# adon3AA.net
KiCad netlist of a schematic drawn in EAGLE
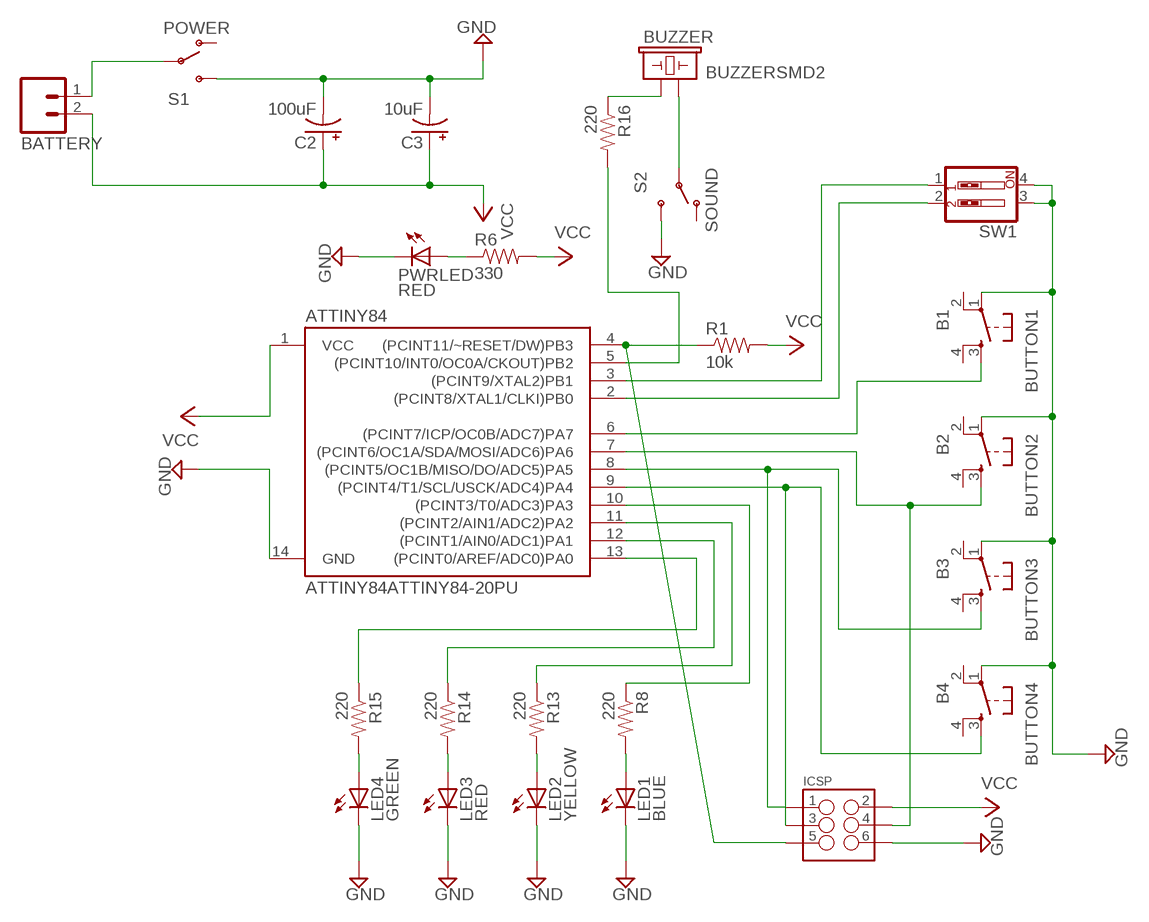
[diagram p0: schematic, sheet 1]

(export (version "E")
  (design (tool "Eeschema 10.0.6"))
  (components
    (comp (ref "ATTINY84")
      (value "ATTINY84ATTINY84-20PU")
      (footprint "eagle-import:DIL14")
      (libsource (lib "eagle-import") (part "ATTINY84ATTINY84-20PU"))
    )
    (comp (ref "BATTERY")
      (value "M02JST-PTH-2")
      (footprint "eagle-import:JST-2-PTH")
      (libsource (lib "eagle-import") (part "M02JST-PTH-2"))
    )
    (comp (ref "BUTTON1")
      (value "B1")
      (footprint "eagle-import:TACTILE-PTH")
      (libsource (lib "eagle-import") (part "TAC_SWITCHPTH"))
    )
    (comp (ref "BUTTON2")
      (value "B2")
      (footprint "eagle-import:TACTILE-PTH")
      (libsource (lib "eagle-import") (part "TAC_SWITCHPTH"))
    )
    (comp (ref "BUTTON3")
      (value "B3")
      (footprint "eagle-import:TACTILE-PTH")
      (libsource (lib "eagle-import") (part "TAC_SWITCHPTH"))
    )
    (comp (ref "BUTTON4")
      (value "B4")
      (footprint "eagle-import:TACTILE-PTH")
      (libsource (lib "eagle-import") (part "TAC_SWITCHPTH"))
    )
    (comp (ref "BUZZER")
      (value "BUZZERSMD2")
      (footprint "eagle-import:BUZZER-CCV")
      (libsource (lib "eagle-import") (part "BUZZERSMD2"))
    )
    (comp (ref "C2")
      (value "100uF")
      (footprint "eagle-import:CPOL-RADIAL-100UF-25V")
      (libsource (lib "eagle-import") (part "CAP_POLPTH1"))
    )
    (comp (ref "C3")
      (value "10uF")
      (footprint "eagle-import:CPOL-RADIAL-10UF-25V")
      (libsource (lib "eagle-import") (part "CAP_POLPTH2"))
    )
    (comp (ref "ICSP")
      (value "M03X2NO_SILK")
      (footprint "eagle-import:2X3-NS")
      (libsource (lib "eagle-import") (part "M03X2NO_SILK"))
    )
    (comp (ref "LED1")
      (value "BLUE")
      (footprint "eagle-import:LED5MM")
      (libsource (lib "eagle-import") (part "LED5MM"))
    )
    (comp (ref "LED2")
      (value "YELLOW")
      (footprint "eagle-import:LED5MM")
      (libsource (lib "eagle-import") (part "LED5MM"))
    )
    (comp (ref "LED3")
      (value "RED")
      (footprint "eagle-import:LED5MM")
      (libsource (lib "eagle-import") (part "LED5MM"))
    )
    (comp (ref "LED4")
      (value "GREEN")
      (footprint "eagle-import:LED5MM")
      (libsource (lib "eagle-import") (part "LED5MM"))
    )
    (comp (ref "PWRLED")
      (value "RED")
      (footprint "eagle-import:LED3MM")
      (libsource (lib "eagle-import") (part "LED3MM"))
    )
    (comp (ref "R1")
      (value "10k")
      (footprint "eagle-import:AXIAL-0.4")
      (libsource (lib "eagle-import") (part "RESISTORPTH-1/4W"))
    )
    (comp (ref "R6")
      (value "330")
      (footprint "eagle-import:AXIAL-0.4")
      (libsource (lib "eagle-import") (part "RESISTORPTH-1/4W"))
    )
    (comp (ref "R8")
      (value "220")
      (footprint "eagle-import:AXIAL-0.4")
      (libsource (lib "eagle-import") (part "RESISTORPTH-1/4W"))
    )
    (comp (ref "R13")
      (value "220")
      (footprint "eagle-import:AXIAL-0.4")
      (libsource (lib "eagle-import") (part "RESISTORPTH-1/4W"))
    )
    (comp (ref "R14")
      (value "220")
      (footprint "eagle-import:AXIAL-0.4")
      (libsource (lib "eagle-import") (part "RESISTORPTH-1/4W"))
    )
    (comp (ref "R15")
      (value "220")
      (footprint "eagle-import:AXIAL-0.4")
      (libsource (lib "eagle-import") (part "RESISTORPTH-1/4W"))
    )
    (comp (ref "R16")
      (value "220")
      (footprint "eagle-import:AXIAL-0.4")
      (libsource (lib "eagle-import") (part "RESISTORPTH-1/4W"))
    )
    (comp (ref "S1")
      (value "POWER")
      (footprint "eagle-import:SWITCH-SPDT_LOCK.007S")
      (libsource (lib "eagle-import") (part "SWITCH-SPDTPTH_LOCK"))
    )
    (comp (ref "S2")
      (value "SOUND")
      (footprint "eagle-import:SWITCH-SPDT_LOCK.007S")
      (libsource (lib "eagle-import") (part "SWITCH-SPDTPTH_LOCK"))
    )
    (comp (ref "SW1")
      (value "SW_DIP-2")
      (footprint "eagle-import:EDG-02")
      (libsource (lib "eagle-import") (part "SW_DIP-2"))
    )
  )
  (nets
    (net (code "1") (name "GND") (class "Default")
      (node (ref "ATTINY84") (pin "14") (pinfunction "GND_14") (pintype "bidirectional"))
      (node (ref "BUTTON1") (pin "1") (pinfunction "1_1") (pintype "passive"))
      (node (ref "BUTTON2") (pin "1") (pinfunction "1_1") (pintype "passive"))
      (node (ref "BUTTON3") (pin "1") (pinfunction "1_1") (pintype "passive"))
      (node (ref "BUTTON4") (pin "1") (pinfunction "1_1") (pintype "passive"))
      (node (ref "C2") (pin "2") (pinfunction "-_2") (pintype "passive"))
      (node (ref "C3") (pin "2") (pinfunction "-_2") (pintype "passive"))
      (node (ref "ICSP") (pin "6") (pinfunction "6_6") (pintype "bidirectional"))
      (node (ref "LED1") (pin "K") (pinfunction "C_K") (pintype "passive"))
      (node (ref "LED2") (pin "K") (pinfunction "C_K") (pintype "passive"))
      (node (ref "LED3") (pin "K") (pinfunction "C_K") (pintype "passive"))
      (node (ref "LED4") (pin "K") (pinfunction "C_K") (pintype "passive"))
      (node (ref "PWRLED") (pin "K") (pinfunction "C_K") (pintype "passive"))
      (node (ref "S1") (pin "3") (pinfunction "S_3") (pintype "passive"))
      (node (ref "S2") (pin "3") (pinfunction "S_3") (pintype "passive"))
      (node (ref "SW1") (pin "3") (pinfunction "3_3") (pintype "passive"))
      (node (ref "SW1") (pin "4") (pinfunction "4_4") (pintype "passive"))
    )
    (net (code "2") (name "Net-(ATTINY84-(PCINT0{slash}AREF{slash}ADC0)PA0)") (class "Default")
      (node (ref "ATTINY84") (pin "13") (pinfunction "(PCINT0/AREF/ADC0)PA0_13") (pintype "bidirectional"))
      (node (ref "R15") (pin "P$1") (pinfunction "1_P$1") (pintype "passive"))
    )
    (net (code "3") (name "Net-(ATTINY84-(PCINT1{slash}AIN0{slash}ADC1)PA1)") (class "Default")
      (node (ref "ATTINY84") (pin "12") (pinfunction "(PCINT1/AIN0/ADC1)PA1_12") (pintype "bidirectional"))
      (node (ref "R14") (pin "P$1") (pinfunction "1_P$1") (pintype "passive"))
    )
    (net (code "4") (name "Net-(ATTINY84-(PCINT2{slash}AIN1{slash}ADC2)PA2)") (class "Default")
      (node (ref "ATTINY84") (pin "11") (pinfunction "(PCINT2/AIN1/ADC2)PA2_11") (pintype "bidirectional"))
      (node (ref "R13") (pin "P$1") (pinfunction "1_P$1") (pintype "passive"))
    )
    (net (code "5") (name "Net-(ATTINY84-(PCINT3{slash}T0{slash}ADC3)PA3)") (class "Default")
      (node (ref "ATTINY84") (pin "10") (pinfunction "(PCINT3/T0/ADC3)PA3_10") (pintype "bidirectional"))
      (node (ref "R8") (pin "P$1") (pinfunction "1_P$1") (pintype "passive"))
    )
    (net (code "6") (name "Net-(ATTINY84-(PCINT4{slash}T1{slash}SCL{slash}USCK{slash}ADC4)PA4)") (class "Default")
      (node (ref "ATTINY84") (pin "9") (pinfunction "(PCINT4/T1/SCL/USCK/ADC4)PA4_9") (pintype "bidirectional"))
      (node (ref "BUTTON4") (pin "3") (pinfunction "3_3") (pintype "passive"))
      (node (ref "ICSP") (pin "3") (pinfunction "3_3") (pintype "bidirectional"))
    )
    (net (code "7") (name "Net-(ATTINY84-(PCINT5{slash}OC1B{slash}MISO{slash}DO{slash}ADC5)PA5)") (class "Default")
      (node (ref "ATTINY84") (pin "8") (pinfunction "(PCINT5/OC1B/MISO/DO/ADC5)PA5_8") (pintype "bidirectional"))
      (node (ref "BUTTON3") (pin "3") (pinfunction "3_3") (pintype "passive"))
      (node (ref "ICSP") (pin "1") (pinfunction "1_1") (pintype "bidirectional"))
    )
    (net (code "8") (name "Net-(ATTINY84-(PCINT6{slash}OC1A{slash}SDA{slash}MOSI{slash}ADC6)PA6)") (class "Default")
      (node (ref "ATTINY84") (pin "7") (pinfunction "(PCINT6/OC1A/SDA/MOSI/ADC6)PA6_7") (pintype "bidirectional"))
      (node (ref "BUTTON2") (pin "3") (pinfunction "3_3") (pintype "passive"))
      (node (ref "ICSP") (pin "4") (pinfunction "4_4") (pintype "bidirectional"))
    )
    (net (code "9") (name "Net-(ATTINY84-(PCINT7{slash}ICP{slash}OC0B{slash}ADC7)PA7)") (class "Default")
      (node (ref "ATTINY84") (pin "6") (pinfunction "(PCINT7/ICP/OC0B/ADC7)PA7_6") (pintype "bidirectional"))
      (node (ref "BUTTON1") (pin "3") (pinfunction "3_3") (pintype "passive"))
    )
    (net (code "10") (name "Net-(ATTINY84-(PCINT8{slash}XTAL1{slash}CLKI)PB0)") (class "Default")
      (node (ref "ATTINY84") (pin "2") (pinfunction "(PCINT8/XTAL1/CLKI)PB0_2") (pintype "bidirectional"))
      (node (ref "SW1") (pin "2") (pinfunction "2_2") (pintype "passive"))
    )
    (net (code "11") (name "Net-(ATTINY84-(PCINT9{slash}XTAL2)PB1)") (class "Default")
      (node (ref "ATTINY84") (pin "3") (pinfunction "(PCINT9/XTAL2)PB1_3") (pintype "bidirectional"))
      (node (ref "SW1") (pin "1") (pinfunction "1_1") (pintype "passive"))
    )
    (net (code "12") (name "Net-(ATTINY84-(PCINT10{slash}INT0{slash}OC0A{slash}CKOUT)PB2)") (class "Default")
      (node (ref "ATTINY84") (pin "5") (pinfunction "(PCINT10/INT0/OC0A/CKOUT)PB2_5") (pintype "bidirectional"))
      (node (ref "R16") (pin "P$2") (pinfunction "2_P$2") (pintype "passive"))
    )
    (net (code "13") (name "Net-(ATTINY84-(PCINT11{slash}~{RESET{slash}DW})PB3)") (class "Default")
      (node (ref "ATTINY84") (pin "4") (pinfunction "(PCINT11/~{RESET/DW})PB3_4") (pintype "bidirectional"))
      (node (ref "ICSP") (pin "5") (pinfunction "5_5") (pintype "bidirectional"))
      (node (ref "R1") (pin "P$1") (pinfunction "1_P$1") (pintype "passive"))
    )
    (net (code "14") (name "Net-(BUZZER-1)") (class "Default")
      (node (ref "BUZZER") (pin "+") (pinfunction "1_+") (pintype "passive"))
      (node (ref "R16") (pin "P$1") (pinfunction "1_P$1") (pintype "passive"))
    )
    (net (code "15") (name "Net-(BUZZER-2)") (class "Default")
      (node (ref "BUZZER") (pin "-") (pinfunction "2_-") (pintype "passive"))
      (node (ref "S2") (pin "2") (pinfunction "P_2") (pintype "passive"))
    )
    (net (code "16") (name "Net-(R6-1)") (class "Default")
      (node (ref "PWRLED") (pin "A") (pinfunction "A_A") (pintype "passive"))
      (node (ref "R6") (pin "P$1") (pinfunction "1_P$1") (pintype "passive"))
    )
    (net (code "17") (name "Net-(R8-2)") (class "Default")
      (node (ref "LED1") (pin "A") (pinfunction "A_A") (pintype "passive"))
      (node (ref "R8") (pin "P$2") (pinfunction "2_P$2") (pintype "passive"))
    )
    (net (code "18") (name "Net-(R13-2)") (class "Default")
      (node (ref "LED2") (pin "A") (pinfunction "A_A") (pintype "passive"))
      (node (ref "R13") (pin "P$2") (pinfunction "2_P$2") (pintype "passive"))
    )
    (net (code "19") (name "Net-(R14-2)") (class "Default")
      (node (ref "LED3") (pin "A") (pinfunction "A_A") (pintype "passive"))
      (node (ref "R14") (pin "P$2") (pinfunction "2_P$2") (pintype "passive"))
    )
    (net (code "20") (name "Net-(R15-2)") (class "Default")
      (node (ref "LED4") (pin "A") (pinfunction "A_A") (pintype "passive"))
      (node (ref "R15") (pin "P$2") (pinfunction "2_P$2") (pintype "passive"))
    )
    (net (code "21") (name "Net-(S1-P)") (class "Default")
      (node (ref "BATTERY") (pin "1") (pinfunction "1_1") (pintype "passive"))
      (node (ref "S1") (pin "2") (pinfunction "P_2") (pintype "passive"))
    )
    (net (code "22") (name "VCC") (class "Default")
      (node (ref "ATTINY84") (pin "1") (pinfunction "VCC_1") (pintype "bidirectional"))
      (node (ref "BATTERY") (pin "2") (pinfunction "2_2") (pintype "passive"))
      (node (ref "C2") (pin "1") (pinfunction "+_1") (pintype "passive"))
      (node (ref "C3") (pin "1") (pinfunction "+_1") (pintype "passive"))
      (node (ref "ICSP") (pin "2") (pinfunction "2_2") (pintype "bidirectional"))
      (node (ref "R1") (pin "P$2") (pinfunction "2_P$2") (pintype "passive"))
      (node (ref "R6") (pin "P$2") (pinfunction "2_P$2") (pintype "passive"))
    )
    (net (code "23") (name "unconnected-(BUTTON1-Pad2)") (class "Default")
      (node (ref "BUTTON1") (pin "2") (pinfunction "2_2") (pintype "passive"))
    )
    (net (code "24") (name "unconnected-(BUTTON1-Pad4)") (class "Default")
      (node (ref "BUTTON1") (pin "4") (pinfunction "4_4") (pintype "passive"))
    )
    (net (code "25") (name "unconnected-(BUTTON2-Pad2)") (class "Default")
      (node (ref "BUTTON2") (pin "2") (pinfunction "2_2") (pintype "passive"))
    )
    (net (code "26") (name "unconnected-(BUTTON2-Pad4)") (class "Default")
      (node (ref "BUTTON2") (pin "4") (pinfunction "4_4") (pintype "passive"))
    )
    (net (code "27") (name "unconnected-(BUTTON3-Pad2)") (class "Default")
      (node (ref "BUTTON3") (pin "2") (pinfunction "2_2") (pintype "passive"))
    )
    (net (code "28") (name "unconnected-(BUTTON3-Pad4)") (class "Default")
      (node (ref "BUTTON3") (pin "4") (pinfunction "4_4") (pintype "passive"))
    )
    (net (code "29") (name "unconnected-(BUTTON4-Pad2)") (class "Default")
      (node (ref "BUTTON4") (pin "2") (pinfunction "2_2") (pintype "passive"))
    )
    (net (code "30") (name "unconnected-(BUTTON4-Pad4)") (class "Default")
      (node (ref "BUTTON4") (pin "4") (pinfunction "4_4") (pintype "passive"))
    )
    (net (code "31") (name "unconnected-(S1-O-Pad1)") (class "Default")
      (node (ref "S1") (pin "1") (pinfunction "O_1") (pintype "passive"))
    )
    (net (code "32") (name "unconnected-(S2-O-Pad1)") (class "Default")
      (node (ref "S2") (pin "1") (pinfunction "O_1") (pintype "passive"))
    )
  )
)
